# LEDBoard.net
KiCad netlist of a schematic drawn in EAGLE
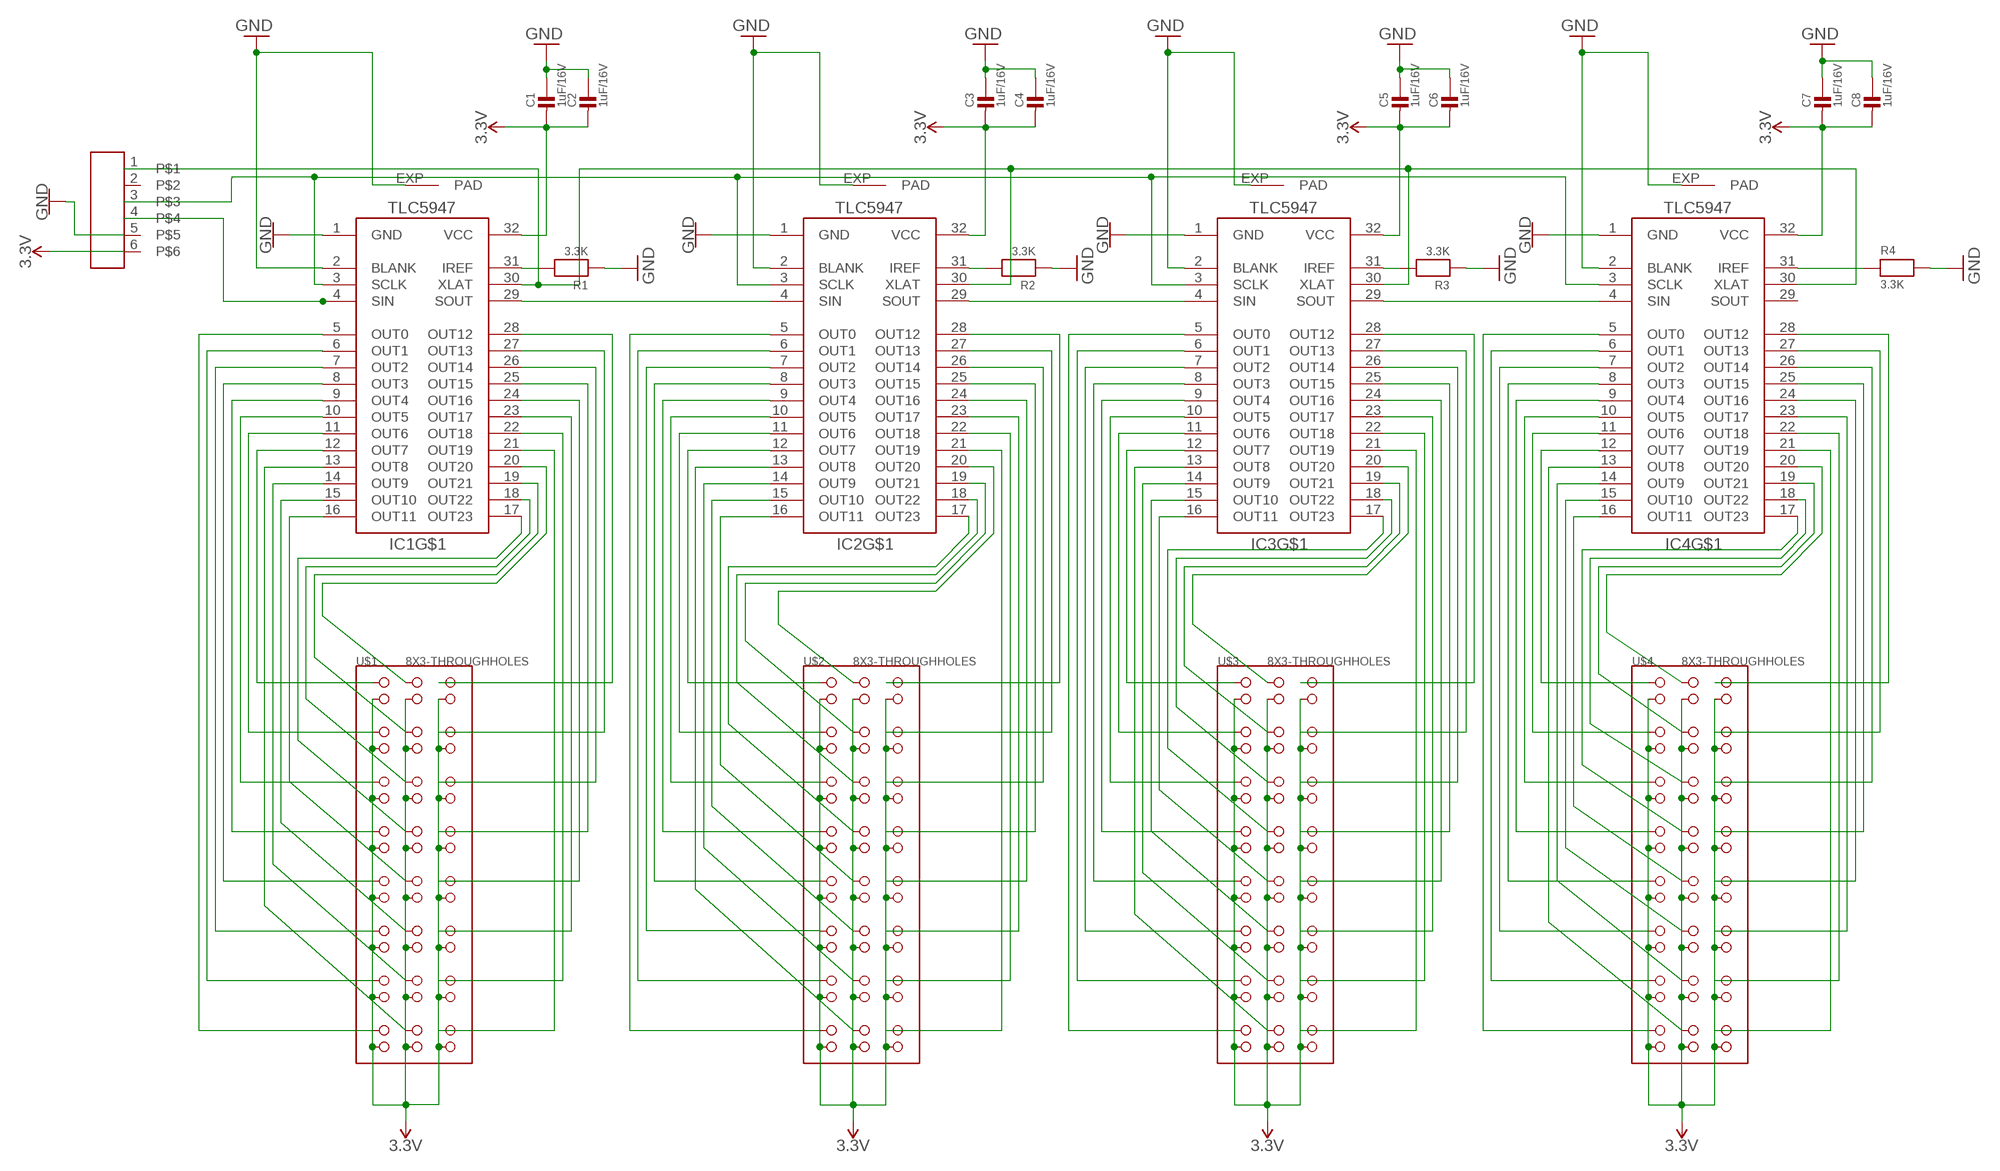
[diagram p0: schematic, sheet 1]

(export (version "E")
  (design (tool "Eeschema 10.0.6"))
  (components
    (comp (ref "C1")
      (value "1uF/16V")
      (footprint "eagle-import:_0805")
      (libsource (lib "eagle-import") (part "CAP_CERAMIC_0805"))
    )
    (comp (ref "C2")
      (value "1uF/16V")
      (footprint "eagle-import:_0805")
      (libsource (lib "eagle-import") (part "CAP_CERAMIC_0805"))
    )
    (comp (ref "C3")
      (value "1uF/16V")
      (footprint "eagle-import:_0805")
      (libsource (lib "eagle-import") (part "CAP_CERAMIC_0805"))
    )
    (comp (ref "C4")
      (value "1uF/16V")
      (footprint "eagle-import:_0805")
      (libsource (lib "eagle-import") (part "CAP_CERAMIC_0805"))
    )
    (comp (ref "C5")
      (value "1uF/16V")
      (footprint "eagle-import:_0805")
      (libsource (lib "eagle-import") (part "CAP_CERAMIC_0805"))
    )
    (comp (ref "C6")
      (value "1uF/16V")
      (footprint "eagle-import:_0805")
      (libsource (lib "eagle-import") (part "CAP_CERAMIC_0805"))
    )
    (comp (ref "C7")
      (value "1uF/16V")
      (footprint "eagle-import:_0805")
      (libsource (lib "eagle-import") (part "CAP_CERAMIC_0805"))
    )
    (comp (ref "C8")
      (value "1uF/16V")
      (footprint "eagle-import:_0805")
      (libsource (lib "eagle-import") (part "CAP_CERAMIC_0805"))
    )
    (comp (ref "IC1")
      (value "TLC5947-DAP")
      (footprint "eagle-import:HTSSOP32DAP")
      (libsource (lib "eagle-import") (part "TLC5947-DAP"))
    )
    (comp (ref "IC2")
      (value "TLC5947-DAP")
      (footprint "eagle-import:HTSSOP32DAP")
      (libsource (lib "eagle-import") (part "TLC5947-DAP"))
    )
    (comp (ref "IC3")
      (value "TLC5947-DAP")
      (footprint "eagle-import:HTSSOP32DAP")
      (libsource (lib "eagle-import") (part "TLC5947-DAP"))
    )
    (comp (ref "IC4")
      (value "TLC5947-DAP")
      (footprint "eagle-import:HTSSOP32DAP")
      (libsource (lib "eagle-import") (part "TLC5947-DAP"))
    )
    (comp (ref "R1")
      (value "3.3K")
      (footprint "eagle-import:_0805")
      (libsource (lib "eagle-import") (part "RESISTOR_0805"))
    )
    (comp (ref "R2")
      (value "3.3K")
      (footprint "eagle-import:_0805")
      (libsource (lib "eagle-import") (part "RESISTOR_0805"))
    )
    (comp (ref "R3")
      (value "3.3K")
      (footprint "eagle-import:_0805")
      (libsource (lib "eagle-import") (part "RESISTOR_0805"))
    )
    (comp (ref "R4")
      (value "3.3K")
      (footprint "eagle-import:_0805")
      (libsource (lib "eagle-import") (part "RESISTOR_0805"))
    )
    (comp (ref "U$1")
      (value "8X3-THROUGHHOLES")
      (footprint "eagle-import:COLUMNOFTHROUGHHOLES")
      (libsource (lib "eagle-import") (part "8X3-THROUGHHOLES"))
    )
    (comp (ref "U$2")
      (value "8X3-THROUGHHOLES")
      (footprint "eagle-import:COLUMNOFTHROUGHHOLES")
      (libsource (lib "eagle-import") (part "8X3-THROUGHHOLES"))
    )
    (comp (ref "U$3")
      (value "8X3-THROUGHHOLES")
      (footprint "eagle-import:COLUMNOFTHROUGHHOLES")
      (libsource (lib "eagle-import") (part "8X3-THROUGHHOLES"))
    )
    (comp (ref "U$4")
      (value "8X3-THROUGHHOLES")
      (footprint "eagle-import:COLUMNOFTHROUGHHOLES")
      (libsource (lib "eagle-import") (part "8X3-THROUGHHOLES"))
    )
    (comp (ref "U$5")
      (value "CONNECTOR_6PIN")
      (footprint "eagle-import:CONNECTOR_6PIN")
      (libsource (lib "eagle-import") (part "CONNECTOR_6PIN"))
    )
  )
  (nets
    (net (code "1") (name "3.3V") (class "Default")
      (node (ref "C1") (pin "2") (pinfunction "P$2_2") (pintype "passive"))
      (node (ref "C2") (pin "2") (pinfunction "P$2_2") (pintype "passive"))
      (node (ref "C3") (pin "2") (pinfunction "P$2_2") (pintype "passive"))
      (node (ref "C4") (pin "2") (pinfunction "P$2_2") (pintype "passive"))
      (node (ref "C5") (pin "2") (pinfunction "P$2_2") (pintype "passive"))
      (node (ref "C6") (pin "2") (pinfunction "P$2_2") (pintype "passive"))
      (node (ref "C7") (pin "2") (pinfunction "P$2_2") (pintype "passive"))
      (node (ref "C8") (pin "2") (pinfunction "P$2_2") (pintype "passive"))
      (node (ref "IC1") (pin "32") (pinfunction "VCC_32") (pintype "power_in"))
      (node (ref "IC2") (pin "32") (pinfunction "VCC_32") (pintype "power_in"))
      (node (ref "IC3") (pin "32") (pinfunction "VCC_32") (pintype "power_in"))
      (node (ref "IC4") (pin "32") (pinfunction "VCC_32") (pintype "power_in"))
      (node (ref "U$1") (pin "V0") (pinfunction "V_V0") (pintype "power_in"))
      (node (ref "U$1") (pin "V1") (pinfunction "V_V1") (pintype "power_in"))
      (node (ref "U$1") (pin "V10") (pinfunction "V_V10") (pintype "power_in"))
      (node (ref "U$1") (pin "V11") (pinfunction "V_V11") (pintype "power_in"))
      (node (ref "U$1") (pin "V12") (pinfunction "V_V12") (pintype "power_in"))
      (node (ref "U$1") (pin "V13") (pinfunction "V_V13") (pintype "power_in"))
      (node (ref "U$1") (pin "V14") (pinfunction "V_V14") (pintype "power_in"))
      (node (ref "U$1") (pin "V15") (pinfunction "V_V15") (pintype "power_in"))
      (node (ref "U$1") (pin "V16") (pinfunction "V_V16") (pintype "power_in"))
      (node (ref "U$1") (pin "V17") (pinfunction "V_V17") (pintype "power_in"))
      (node (ref "U$1") (pin "V18") (pinfunction "V_V18") (pintype "power_in"))
      (node (ref "U$1") (pin "V19") (pinfunction "V_V19") (pintype "power_in"))
      (node (ref "U$1") (pin "V2") (pinfunction "V_V2") (pintype "power_in"))
      (node (ref "U$1") (pin "V20") (pinfunction "V_V20") (pintype "power_in"))
      (node (ref "U$1") (pin "V21") (pinfunction "V_V21") (pintype "power_in"))
      (node (ref "U$1") (pin "V22") (pinfunction "V_V22") (pintype "power_in"))
      (node (ref "U$1") (pin "V23") (pinfunction "V_V23") (pintype "power_in"))
      (node (ref "U$1") (pin "V3") (pinfunction "V_V3") (pintype "power_in"))
      (node (ref "U$1") (pin "V4") (pinfunction "V_V4") (pintype "power_in"))
      (node (ref "U$1") (pin "V5") (pinfunction "V_V5") (pintype "power_in"))
      (node (ref "U$1") (pin "V6") (pinfunction "V_V6") (pintype "power_in"))
      (node (ref "U$1") (pin "V7") (pinfunction "V_V7") (pintype "power_in"))
      (node (ref "U$1") (pin "V8") (pinfunction "V_V8") (pintype "power_in"))
      (node (ref "U$1") (pin "V9") (pinfunction "V_V9") (pintype "power_in"))
      (node (ref "U$2") (pin "V0") (pinfunction "V_V0") (pintype "power_in"))
      (node (ref "U$2") (pin "V1") (pinfunction "V_V1") (pintype "power_in"))
      (node (ref "U$2") (pin "V10") (pinfunction "V_V10") (pintype "power_in"))
      (node (ref "U$2") (pin "V11") (pinfunction "V_V11") (pintype "power_in"))
      (node (ref "U$2") (pin "V12") (pinfunction "V_V12") (pintype "power_in"))
      (node (ref "U$2") (pin "V13") (pinfunction "V_V13") (pintype "power_in"))
      (node (ref "U$2") (pin "V14") (pinfunction "V_V14") (pintype "power_in"))
      (node (ref "U$2") (pin "V15") (pinfunction "V_V15") (pintype "power_in"))
      (node (ref "U$2") (pin "V16") (pinfunction "V_V16") (pintype "power_in"))
      (node (ref "U$2") (pin "V17") (pinfunction "V_V17") (pintype "power_in"))
      (node (ref "U$2") (pin "V18") (pinfunction "V_V18") (pintype "power_in"))
      (node (ref "U$2") (pin "V19") (pinfunction "V_V19") (pintype "power_in"))
      (node (ref "U$2") (pin "V2") (pinfunction "V_V2") (pintype "power_in"))
      (node (ref "U$2") (pin "V20") (pinfunction "V_V20") (pintype "power_in"))
      (node (ref "U$2") (pin "V21") (pinfunction "V_V21") (pintype "power_in"))
      (node (ref "U$2") (pin "V22") (pinfunction "V_V22") (pintype "power_in"))
      (node (ref "U$2") (pin "V23") (pinfunction "V_V23") (pintype "power_in"))
      (node (ref "U$2") (pin "V3") (pinfunction "V_V3") (pintype "power_in"))
      (node (ref "U$2") (pin "V4") (pinfunction "V_V4") (pintype "power_in"))
      (node (ref "U$2") (pin "V5") (pinfunction "V_V5") (pintype "power_in"))
      (node (ref "U$2") (pin "V6") (pinfunction "V_V6") (pintype "power_in"))
      (node (ref "U$2") (pin "V7") (pinfunction "V_V7") (pintype "power_in"))
      (node (ref "U$2") (pin "V8") (pinfunction "V_V8") (pintype "power_in"))
      (node (ref "U$2") (pin "V9") (pinfunction "V_V9") (pintype "power_in"))
      (node (ref "U$3") (pin "V0") (pinfunction "V_V0") (pintype "power_in"))
      (node (ref "U$3") (pin "V1") (pinfunction "V_V1") (pintype "power_in"))
      (node (ref "U$3") (pin "V10") (pinfunction "V_V10") (pintype "power_in"))
      (node (ref "U$3") (pin "V11") (pinfunction "V_V11") (pintype "power_in"))
      (node (ref "U$3") (pin "V12") (pinfunction "V_V12") (pintype "power_in"))
      (node (ref "U$3") (pin "V13") (pinfunction "V_V13") (pintype "power_in"))
      (node (ref "U$3") (pin "V14") (pinfunction "V_V14") (pintype "power_in"))
      (node (ref "U$3") (pin "V15") (pinfunction "V_V15") (pintype "power_in"))
      (node (ref "U$3") (pin "V16") (pinfunction "V_V16") (pintype "power_in"))
      (node (ref "U$3") (pin "V17") (pinfunction "V_V17") (pintype "power_in"))
      (node (ref "U$3") (pin "V18") (pinfunction "V_V18") (pintype "power_in"))
      (node (ref "U$3") (pin "V19") (pinfunction "V_V19") (pintype "power_in"))
      (node (ref "U$3") (pin "V2") (pinfunction "V_V2") (pintype "power_in"))
      (node (ref "U$3") (pin "V20") (pinfunction "V_V20") (pintype "power_in"))
      (node (ref "U$3") (pin "V21") (pinfunction "V_V21") (pintype "power_in"))
      (node (ref "U$3") (pin "V22") (pinfunction "V_V22") (pintype "power_in"))
      (node (ref "U$3") (pin "V23") (pinfunction "V_V23") (pintype "power_in"))
      (node (ref "U$3") (pin "V3") (pinfunction "V_V3") (pintype "power_in"))
      (node (ref "U$3") (pin "V4") (pinfunction "V_V4") (pintype "power_in"))
      (node (ref "U$3") (pin "V5") (pinfunction "V_V5") (pintype "power_in"))
      (node (ref "U$3") (pin "V6") (pinfunction "V_V6") (pintype "power_in"))
      (node (ref "U$3") (pin "V7") (pinfunction "V_V7") (pintype "power_in"))
      (node (ref "U$3") (pin "V8") (pinfunction "V_V8") (pintype "power_in"))
      (node (ref "U$3") (pin "V9") (pinfunction "V_V9") (pintype "power_in"))
      (node (ref "U$4") (pin "V0") (pinfunction "V_V0") (pintype "power_in"))
      (node (ref "U$4") (pin "V1") (pinfunction "V_V1") (pintype "power_in"))
      (node (ref "U$4") (pin "V10") (pinfunction "V_V10") (pintype "power_in"))
      (node (ref "U$4") (pin "V11") (pinfunction "V_V11") (pintype "power_in"))
      (node (ref "U$4") (pin "V12") (pinfunction "V_V12") (pintype "power_in"))
      (node (ref "U$4") (pin "V13") (pinfunction "V_V13") (pintype "power_in"))
      (node (ref "U$4") (pin "V14") (pinfunction "V_V14") (pintype "power_in"))
      (node (ref "U$4") (pin "V15") (pinfunction "V_V15") (pintype "power_in"))
      (node (ref "U$4") (pin "V16") (pinfunction "V_V16") (pintype "power_in"))
      (node (ref "U$4") (pin "V17") (pinfunction "V_V17") (pintype "power_in"))
      (node (ref "U$4") (pin "V18") (pinfunction "V_V18") (pintype "power_in"))
      (node (ref "U$4") (pin "V19") (pinfunction "V_V19") (pintype "power_in"))
      (node (ref "U$4") (pin "V2") (pinfunction "V_V2") (pintype "power_in"))
      (node (ref "U$4") (pin "V20") (pinfunction "V_V20") (pintype "power_in"))
      (node (ref "U$4") (pin "V21") (pinfunction "V_V21") (pintype "power_in"))
      (node (ref "U$4") (pin "V22") (pinfunction "V_V22") (pintype "power_in"))
      (node (ref "U$4") (pin "V23") (pinfunction "V_V23") (pintype "power_in"))
      (node (ref "U$4") (pin "V3") (pinfunction "V_V3") (pintype "power_in"))
      (node (ref "U$4") (pin "V4") (pinfunction "V_V4") (pintype "power_in"))
      (node (ref "U$4") (pin "V5") (pinfunction "V_V5") (pintype "power_in"))
      (node (ref "U$4") (pin "V6") (pinfunction "V_V6") (pintype "power_in"))
      (node (ref "U$4") (pin "V7") (pinfunction "V_V7") (pintype "power_in"))
      (node (ref "U$4") (pin "V8") (pinfunction "V_V8") (pintype "power_in"))
      (node (ref "U$4") (pin "V9") (pinfunction "V_V9") (pintype "power_in"))
      (node (ref "U$5") (pin "6") (pinfunction "P$6_6") (pintype "bidirectional"))
    )
    (net (code "2") (name "GND") (class "Default")
      (node (ref "C1") (pin "1") (pinfunction "P$1_1") (pintype "passive"))
      (node (ref "C2") (pin "1") (pinfunction "P$1_1") (pintype "passive"))
      (node (ref "C3") (pin "1") (pinfunction "P$1_1") (pintype "passive"))
      (node (ref "C4") (pin "1") (pinfunction "P$1_1") (pintype "passive"))
      (node (ref "C5") (pin "1") (pinfunction "P$1_1") (pintype "passive"))
      (node (ref "C6") (pin "1") (pinfunction "P$1_1") (pintype "passive"))
      (node (ref "C7") (pin "1") (pinfunction "P$1_1") (pintype "passive"))
      (node (ref "C8") (pin "1") (pinfunction "P$1_1") (pintype "passive"))
      (node (ref "IC1") (pin "1") (pinfunction "GND_1") (pintype "power_in"))
      (node (ref "IC1") (pin "2") (pinfunction "BLANK_2") (pintype "input"))
      (node (ref "IC1") (pin "EXP") (pinfunction "PAD_EXP") (pintype "passive"))
      (node (ref "IC2") (pin "1") (pinfunction "GND_1") (pintype "power_in"))
      (node (ref "IC2") (pin "2") (pinfunction "BLANK_2") (pintype "input"))
      (node (ref "IC2") (pin "EXP") (pinfunction "PAD_EXP") (pintype "passive"))
      (node (ref "IC3") (pin "1") (pinfunction "GND_1") (pintype "power_in"))
      (node (ref "IC3") (pin "2") (pinfunction "BLANK_2") (pintype "input"))
      (node (ref "IC3") (pin "EXP") (pinfunction "PAD_EXP") (pintype "passive"))
      (node (ref "IC4") (pin "1") (pinfunction "GND_1") (pintype "power_in"))
      (node (ref "IC4") (pin "2") (pinfunction "BLANK_2") (pintype "input"))
      (node (ref "IC4") (pin "EXP") (pinfunction "PAD_EXP") (pintype "passive"))
      (node (ref "R1") (pin "1") (pinfunction "1_1") (pintype "passive"))
      (node (ref "R2") (pin "1") (pinfunction "1_1") (pintype "passive"))
      (node (ref "R3") (pin "1") (pinfunction "1_1") (pintype "passive"))
      (node (ref "R4") (pin "2") (pinfunction "2_2") (pintype "passive"))
      (node (ref "U$5") (pin "5") (pinfunction "P$5_5") (pintype "bidirectional"))
    )
    (net (code "3") (name "Net-(IC1A-IREF)") (class "Default")
      (node (ref "IC1") (pin "31") (pinfunction "IREF_31") (pintype "bidirectional"))
      (node (ref "R1") (pin "2") (pinfunction "2_2") (pintype "passive"))
    )
    (net (code "4") (name "Net-(IC1A-OUT0)") (class "Default")
      (node (ref "IC1") (pin "5") (pinfunction "OUT0_5") (pintype "open_collector"))
      (node (ref "U$1") (pin "0") (pinfunction "0_0") (pintype "power_in"))
    )
    (net (code "5") (name "Net-(IC1A-OUT1)") (class "Default")
      (node (ref "IC1") (pin "6") (pinfunction "OUT1_6") (pintype "open_collector"))
      (node (ref "U$1") (pin "1") (pinfunction "1_1") (pintype "power_in"))
    )
    (net (code "6") (name "Net-(IC1A-OUT2)") (class "Default")
      (node (ref "IC1") (pin "7") (pinfunction "OUT2_7") (pintype "open_collector"))
      (node (ref "U$1") (pin "2") (pinfunction "2_2") (pintype "power_in"))
    )
    (net (code "7") (name "Net-(IC1A-OUT3)") (class "Default")
      (node (ref "IC1") (pin "8") (pinfunction "OUT3_8") (pintype "open_collector"))
      (node (ref "U$1") (pin "3") (pinfunction "3_3") (pintype "power_in"))
    )
    (net (code "8") (name "Net-(IC1A-OUT4)") (class "Default")
      (node (ref "IC1") (pin "9") (pinfunction "OUT4_9") (pintype "open_collector"))
      (node (ref "U$1") (pin "4") (pinfunction "4_4") (pintype "power_in"))
    )
    (net (code "9") (name "Net-(IC1A-OUT5)") (class "Default")
      (node (ref "IC1") (pin "10") (pinfunction "OUT5_10") (pintype "open_collector"))
      (node (ref "U$1") (pin "5") (pinfunction "5_5") (pintype "power_in"))
    )
    (net (code "10") (name "Net-(IC1A-OUT6)") (class "Default")
      (node (ref "IC1") (pin "11") (pinfunction "OUT6_11") (pintype "open_collector"))
      (node (ref "U$1") (pin "6") (pinfunction "6_6") (pintype "power_in"))
    )
    (net (code "11") (name "Net-(IC1A-OUT7)") (class "Default")
      (node (ref "IC1") (pin "12") (pinfunction "OUT7_12") (pintype "open_collector"))
      (node (ref "U$1") (pin "7") (pinfunction "7_7") (pintype "power_in"))
    )
    (net (code "12") (name "Net-(IC1A-OUT8)") (class "Default")
      (node (ref "IC1") (pin "13") (pinfunction "OUT8_13") (pintype "open_collector"))
      (node (ref "U$1") (pin "8") (pinfunction "8_8") (pintype "power_in"))
    )
    (net (code "13") (name "Net-(IC1A-OUT9)") (class "Default")
      (node (ref "IC1") (pin "14") (pinfunction "OUT9_14") (pintype "open_collector"))
      (node (ref "U$1") (pin "9") (pinfunction "9_9") (pintype "power_in"))
    )
    (net (code "14") (name "Net-(IC1A-OUT10)") (class "Default")
      (node (ref "IC1") (pin "15") (pinfunction "OUT10_15") (pintype "open_collector"))
      (node (ref "U$1") (pin "10") (pinfunction "10_10") (pintype "power_in"))
    )
    (net (code "15") (name "Net-(IC1A-OUT11)") (class "Default")
      (node (ref "IC1") (pin "16") (pinfunction "OUT11_16") (pintype "open_collector"))
      (node (ref "U$1") (pin "11") (pinfunction "11_11") (pintype "power_in"))
    )
    (net (code "16") (name "Net-(IC1A-OUT12)") (class "Default")
      (node (ref "IC1") (pin "28") (pinfunction "OUT12_28") (pintype "open_collector"))
      (node (ref "U$1") (pin "23") (pinfunction "23_23") (pintype "power_in"))
    )
    (net (code "17") (name "Net-(IC1A-OUT13)") (class "Default")
      (node (ref "IC1") (pin "27") (pinfunction "OUT13_27") (pintype "open_collector"))
      (node (ref "U$1") (pin "22") (pinfunction "22_22") (pintype "power_in"))
    )
    (net (code "18") (name "Net-(IC1A-OUT14)") (class "Default")
      (node (ref "IC1") (pin "26") (pinfunction "OUT14_26") (pintype "open_collector"))
      (node (ref "U$1") (pin "21") (pinfunction "21_21") (pintype "power_in"))
    )
    (net (code "19") (name "Net-(IC1A-OUT15)") (class "Default")
      (node (ref "IC1") (pin "25") (pinfunction "OUT15_25") (pintype "open_collector"))
      (node (ref "U$1") (pin "20") (pinfunction "20_20") (pintype "power_in"))
    )
    (net (code "20") (name "Net-(IC1A-OUT16)") (class "Default")
      (node (ref "IC1") (pin "24") (pinfunction "OUT16_24") (pintype "open_collector"))
      (node (ref "U$1") (pin "19") (pinfunction "19_19") (pintype "power_in"))
    )
    (net (code "21") (name "Net-(IC1A-OUT17)") (class "Default")
      (node (ref "IC1") (pin "23") (pinfunction "OUT17_23") (pintype "open_collector"))
      (node (ref "U$1") (pin "18") (pinfunction "18_18") (pintype "power_in"))
    )
    (net (code "22") (name "Net-(IC1A-OUT18)") (class "Default")
      (node (ref "IC1") (pin "22") (pinfunction "OUT18_22") (pintype "open_collector"))
      (node (ref "U$1") (pin "17") (pinfunction "17_17") (pintype "power_in"))
    )
    (net (code "23") (name "Net-(IC1A-OUT19)") (class "Default")
      (node (ref "IC1") (pin "21") (pinfunction "OUT19_21") (pintype "open_collector"))
      (node (ref "U$1") (pin "16") (pinfunction "16_16") (pintype "power_in"))
    )
    (net (code "24") (name "Net-(IC1A-OUT20)") (class "Default")
      (node (ref "IC1") (pin "20") (pinfunction "OUT20_20") (pintype "open_collector"))
      (node (ref "U$1") (pin "15") (pinfunction "15_15") (pintype "power_in"))
    )
    (net (code "25") (name "Net-(IC1A-OUT21)") (class "Default")
      (node (ref "IC1") (pin "19") (pinfunction "OUT21_19") (pintype "open_collector"))
      (node (ref "U$1") (pin "14") (pinfunction "14_14") (pintype "power_in"))
    )
    (net (code "26") (name "Net-(IC1A-OUT22)") (class "Default")
      (node (ref "IC1") (pin "18") (pinfunction "OUT22_18") (pintype "open_collector"))
      (node (ref "U$1") (pin "13") (pinfunction "13_13") (pintype "power_in"))
    )
    (net (code "27") (name "Net-(IC1A-OUT23)") (class "Default")
      (node (ref "IC1") (pin "17") (pinfunction "OUT23_17") (pintype "open_collector"))
      (node (ref "U$1") (pin "12") (pinfunction "12_12") (pintype "power_in"))
    )
    (net (code "28") (name "Net-(IC1A-SCLK)") (class "Default")
      (node (ref "IC1") (pin "3") (pinfunction "SCLK_3") (pintype "input"))
      (node (ref "IC2") (pin "3") (pinfunction "SCLK_3") (pintype "input"))
      (node (ref "IC3") (pin "3") (pinfunction "SCLK_3") (pintype "input"))
      (node (ref "IC4") (pin "3") (pinfunction "SCLK_3") (pintype "input"))
      (node (ref "U$5") (pin "3") (pinfunction "P$3_3") (pintype "bidirectional"))
    )
    (net (code "29") (name "Net-(IC1A-SIN)") (class "Default")
      (node (ref "IC1") (pin "4") (pinfunction "SIN_4") (pintype "input"))
      (node (ref "U$5") (pin "4") (pinfunction "P$4_4") (pintype "bidirectional"))
    )
    (net (code "30") (name "Net-(IC1A-SOUT)") (class "Default")
      (node (ref "IC1") (pin "29") (pinfunction "SOUT_29") (pintype "output"))
      (node (ref "IC2") (pin "4") (pinfunction "SIN_4") (pintype "input"))
    )
    (net (code "31") (name "Net-(IC1A-XLAT)") (class "Default")
      (node (ref "IC1") (pin "30") (pinfunction "XLAT_30") (pintype "input"))
      (node (ref "IC2") (pin "30") (pinfunction "XLAT_30") (pintype "input"))
      (node (ref "IC3") (pin "30") (pinfunction "XLAT_30") (pintype "input"))
      (node (ref "IC4") (pin "30") (pinfunction "XLAT_30") (pintype "input"))
      (node (ref "U$5") (pin "1") (pinfunction "P$1_1") (pintype "bidirectional"))
    )
    (net (code "32") (name "Net-(IC2A-IREF)") (class "Default")
      (node (ref "IC2") (pin "31") (pinfunction "IREF_31") (pintype "bidirectional"))
      (node (ref "R2") (pin "2") (pinfunction "2_2") (pintype "passive"))
    )
    (net (code "33") (name "Net-(IC2A-OUT0)") (class "Default")
      (node (ref "IC2") (pin "5") (pinfunction "OUT0_5") (pintype "open_collector"))
      (node (ref "U$2") (pin "0") (pinfunction "0_0") (pintype "power_in"))
    )
    (net (code "34") (name "Net-(IC2A-OUT1)") (class "Default")
      (node (ref "IC2") (pin "6") (pinfunction "OUT1_6") (pintype "open_collector"))
      (node (ref "U$2") (pin "1") (pinfunction "1_1") (pintype "power_in"))
    )
    (net (code "35") (name "Net-(IC2A-OUT2)") (class "Default")
      (node (ref "IC2") (pin "7") (pinfunction "OUT2_7") (pintype "open_collector"))
      (node (ref "U$2") (pin "2") (pinfunction "2_2") (pintype "power_in"))
    )
    (net (code "36") (name "Net-(IC2A-OUT3)") (class "Default")
      (node (ref "IC2") (pin "8") (pinfunction "OUT3_8") (pintype "open_collector"))
      (node (ref "U$2") (pin "3") (pinfunction "3_3") (pintype "power_in"))
    )
    (net (code "37") (name "Net-(IC2A-OUT4)") (class "Default")
      (node (ref "IC2") (pin "9") (pinfunction "OUT4_9") (pintype "open_collector"))
      (node (ref "U$2") (pin "4") (pinfunction "4_4") (pintype "power_in"))
    )
    (net (code "38") (name "Net-(IC2A-OUT5)") (class "Default")
      (node (ref "IC2") (pin "10") (pinfunction "OUT5_10") (pintype "open_collector"))
      (node (ref "U$2") (pin "5") (pinfunction "5_5") (pintype "power_in"))
    )
    (net (code "39") (name "Net-(IC2A-OUT6)") (class "Default")
      (node (ref "IC2") (pin "11") (pinfunction "OUT6_11") (pintype "open_collector"))
      (node (ref "U$2") (pin "6") (pinfunction "6_6") (pintype "power_in"))
    )
    (net (code "40") (name "Net-(IC2A-OUT7)") (class "Default")
      (node (ref "IC2") (pin "12") (pinfunction "OUT7_12") (pintype "open_collector"))
      (node (ref "U$2") (pin "7") (pinfunction "7_7") (pintype "power_in"))
    )
    (net (code "41") (name "Net-(IC2A-OUT8)") (class "Default")
      (node (ref "IC2") (pin "13") (pinfunction "OUT8_13") (pintype "open_collector"))
      (node (ref "U$2") (pin "8") (pinfunction "8_8") (pintype "power_in"))
    )
    (net (code "42") (name "Net-(IC2A-OUT9)") (class "Default")
      (node (ref "IC2") (pin "14") (pinfunction "OUT9_14") (pintype "open_collector"))
      (node (ref "U$2") (pin "9") (pinfunction "9_9") (pintype "power_in"))
    )
    (net (code "43") (name "Net-(IC2A-OUT10)") (class "Default")
      (node (ref "IC2") (pin "15") (pinfunction "OUT10_15") (pintype "open_collector"))
      (node (ref "U$2") (pin "10") (pinfunction "10_10") (pintype "power_in"))
    )
    (net (code "44") (name "Net-(IC2A-OUT11)") (class "Default")
      (node (ref "IC2") (pin "16") (pinfunction "OUT11_16") (pintype "open_collector"))
      (node (ref "U$2") (pin "11") (pinfunction "11_11") (pintype "power_in"))
    )
    (net (code "45") (name "Net-(IC2A-OUT12)") (class "Default")
      (node (ref "IC2") (pin "28") (pinfunction "OUT12_28") (pintype "open_collector"))
      (node (ref "U$2") (pin "23") (pinfunction "23_23") (pintype "power_in"))
    )
    (net (code "46") (name "Net-(IC2A-OUT13)") (class "Default")
      (node (ref "IC2") (pin "27") (pinfunction "OUT13_27") (pintype "open_collector"))
      (node (ref "U$2") (pin "22") (pinfunction "22_22") (pintype "power_in"))
    )
    (net (code "47") (name "Net-(IC2A-OUT14)") (class "Default")
      (node (ref "IC2") (pin "26") (pinfunction "OUT14_26") (pintype "open_collector"))
      (node (ref "U$2") (pin "21") (pinfunction "21_21") (pintype "power_in"))
    )
    (net (code "48") (name "Net-(IC2A-OUT15)") (class "Default")
      (node (ref "IC2") (pin "25") (pinfunction "OUT15_25") (pintype "open_collector"))
      (node (ref "U$2") (pin "20") (pinfunction "20_20") (pintype "power_in"))
    )
    (net (code "49") (name "Net-(IC2A-OUT16)") (class "Default")
      (node (ref "IC2") (pin "24") (pinfunction "OUT16_24") (pintype "open_collector"))
      (node (ref "U$2") (pin "19") (pinfunction "19_19") (pintype "power_in"))
    )
    (net (code "50") (name "Net-(IC2A-OUT17)") (class "Default")
      (node (ref "IC2") (pin "23") (pinfunction "OUT17_23") (pintype "open_collector"))
      (node (ref "U$2") (pin "18") (pinfunction "18_18") (pintype "power_in"))
    )
    (net (code "51") (name "Net-(IC2A-OUT18)") (class "Default")
      (node (ref "IC2") (pin "22") (pinfunction "OUT18_22") (pintype "open_collector"))
      (node (ref "U$2") (pin "17") (pinfunction "17_17") (pintype "power_in"))
    )
    (net (code "52") (name "Net-(IC2A-OUT19)") (class "Default")
      (node (ref "IC2") (pin "21") (pinfunction "OUT19_21") (pintype "open_collector"))
      (node (ref "U$2") (pin "16") (pinfunction "16_16") (pintype "power_in"))
    )
    (net (code "53") (name "Net-(IC2A-OUT20)") (class "Default")
      (node (ref "IC2") (pin "20") (pinfunction "OUT20_20") (pintype "open_collector"))
      (node (ref "U$2") (pin "15") (pinfunction "15_15") (pintype "power_in"))
    )
    (net (code "54") (name "Net-(IC2A-OUT21)") (class "Default")
      (node (ref "IC2") (pin "19") (pinfunction "OUT21_19") (pintype "open_collector"))
      (node (ref "U$2") (pin "14") (pinfunction "14_14") (pintype "power_in"))
    )
    (net (code "55") (name "Net-(IC2A-OUT22)") (class "Default")
      (node (ref "IC2") (pin "18") (pinfunction "OUT22_18") (pintype "open_collector"))
      (node (ref "U$2") (pin "13") (pinfunction "13_13") (pintype "power_in"))
    )
    (net (code "56") (name "Net-(IC2A-OUT23)") (class "Default")
      (node (ref "IC2") (pin "17") (pinfunction "OUT23_17") (pintype "open_collector"))
      (node (ref "U$2") (pin "12") (pinfunction "12_12") (pintype "power_in"))
    )
    (net (code "57") (name "Net-(IC2A-SOUT)") (class "Default")
      (node (ref "IC2") (pin "29") (pinfunction "SOUT_29") (pintype "output"))
      (node (ref "IC3") (pin "4") (pinfunction "SIN_4") (pintype "input"))
    )
    (net (code "58") (name "Net-(IC3A-IREF)") (class "Default")
      (node (ref "IC3") (pin "31") (pinfunction "IREF_31") (pintype "bidirectional"))
      (node (ref "R3") (pin "2") (pinfunction "2_2") (pintype "passive"))
    )
    (net (code "59") (name "Net-(IC3A-OUT0)") (class "Default")
      (node (ref "IC3") (pin "5") (pinfunction "OUT0_5") (pintype "open_collector"))
      (node (ref "U$3") (pin "0") (pinfunction "0_0") (pintype "power_in"))
    )
    (net (code "60") (name "Net-(IC3A-OUT1)") (class "Default")
      (node (ref "IC3") (pin "6") (pinfunction "OUT1_6") (pintype "open_collector"))
      (node (ref "U$3") (pin "1") (pinfunction "1_1") (pintype "power_in"))
    )
    (net (code "61") (name "Net-(IC3A-OUT2)") (class "Default")
      (node (ref "IC3") (pin "7") (pinfunction "OUT2_7") (pintype "open_collector"))
      (node (ref "U$3") (pin "2") (pinfunction "2_2") (pintype "power_in"))
    )
    (net (code "62") (name "Net-(IC3A-OUT3)") (class "Default")
      (node (ref "IC3") (pin "8") (pinfunction "OUT3_8") (pintype "open_collector"))
      (node (ref "U$3") (pin "3") (pinfunction "3_3") (pintype "power_in"))
    )
    (net (code "63") (name "Net-(IC3A-OUT4)") (class "Default")
      (node (ref "IC3") (pin "9") (pinfunction "OUT4_9") (pintype "open_collector"))
      (node (ref "U$3") (pin "4") (pinfunction "4_4") (pintype "power_in"))
    )
    (net (code "64") (name "Net-(IC3A-OUT5)") (class "Default")
      (node (ref "IC3") (pin "10") (pinfunction "OUT5_10") (pintype "open_collector"))
      (node (ref "U$3") (pin "5") (pinfunction "5_5") (pintype "power_in"))
    )
    (net (code "65") (name "Net-(IC3A-OUT6)") (class "Default")
      (node (ref "IC3") (pin "11") (pinfunction "OUT6_11") (pintype "open_collector"))
      (node (ref "U$3") (pin "6") (pinfunction "6_6") (pintype "power_in"))
    )
    (net (code "66") (name "Net-(IC3A-OUT7)") (class "Default")
      (node (ref "IC3") (pin "12") (pinfunction "OUT7_12") (pintype "open_collector"))
      (node (ref "U$3") (pin "7") (pinfunction "7_7") (pintype "power_in"))
    )
    (net (code "67") (name "Net-(IC3A-OUT8)") (class "Default")
      (node (ref "IC3") (pin "13") (pinfunction "OUT8_13") (pintype "open_collector"))
      (node (ref "U$3") (pin "8") (pinfunction "8_8") (pintype "power_in"))
    )
    (net (code "68") (name "Net-(IC3A-OUT9)") (class "Default")
      (node (ref "IC3") (pin "14") (pinfunction "OUT9_14") (pintype "open_collector"))
      (node (ref "U$3") (pin "9") (pinfunction "9_9") (pintype "power_in"))
    )
    (net (code "69") (name "Net-(IC3A-OUT10)") (class "Default")
      (node (ref "IC3") (pin "15") (pinfunction "OUT10_15") (pintype "open_collector"))
      (node (ref "U$3") (pin "10") (pinfunction "10_10") (pintype "power_in"))
    )
    (net (code "70") (name "Net-(IC3A-OUT11)") (class "Default")
      (node (ref "IC3") (pin "16") (pinfunction "OUT11_16") (pintype "open_collector"))
      (node (ref "U$3") (pin "11") (pinfunction "11_11") (pintype "power_in"))
    )
    (net (code "71") (name "Net-(IC3A-OUT12)") (class "Default")
      (node (ref "IC3") (pin "28") (pinfunction "OUT12_28") (pintype "open_collector"))
      (node (ref "U$3") (pin "23") (pinfunction "23_23") (pintype "power_in"))
    )
    (net (code "72") (name "Net-(IC3A-OUT13)") (class "Default")
      (node (ref "IC3") (pin "27") (pinfunction "OUT13_27") (pintype "open_collector"))
      (node (ref "U$3") (pin "22") (pinfunction "22_22") (pintype "power_in"))
    )
    (net (code "73") (name "Net-(IC3A-OUT14)") (class "Default")
      (node (ref "IC3") (pin "26") (pinfunction "OUT14_26") (pintype "open_collector"))
      (node (ref "U$3") (pin "21") (pinfunction "21_21") (pintype "power_in"))
    )
    (net (code "74") (name "Net-(IC3A-OUT15)") (class "Default")
      (node (ref "IC3") (pin "25") (pinfunction "OUT15_25") (pintype "open_collector"))
      (node (ref "U$3") (pin "20") (pinfunction "20_20") (pintype "power_in"))
    )
    (net (code "75") (name "Net-(IC3A-OUT16)") (class "Default")
      (node (ref "IC3") (pin "24") (pinfunction "OUT16_24") (pintype "open_collector"))
      (node (ref "U$3") (pin "19") (pinfunction "19_19") (pintype "power_in"))
    )
    (net (code "76") (name "Net-(IC3A-OUT17)") (class "Default")
      (node (ref "IC3") (pin "23") (pinfunction "OUT17_23") (pintype "open_collector"))
      (node (ref "U$3") (pin "18") (pinfunction "18_18") (pintype "power_in"))
    )
    (net (code "77") (name "Net-(IC3A-OUT18)") (class "Default")
      (node (ref "IC3") (pin "22") (pinfunction "OUT18_22") (pintype "open_collector"))
      (node (ref "U$3") (pin "17") (pinfunction "17_17") (pintype "power_in"))
    )
    (net (code "78") (name "Net-(IC3A-OUT19)") (class "Default")
      (node (ref "IC3") (pin "21") (pinfunction "OUT19_21") (pintype "open_collector"))
      (node (ref "U$3") (pin "16") (pinfunction "16_16") (pintype "power_in"))
    )
    (net (code "79") (name "Net-(IC3A-OUT20)") (class "Default")
      (node (ref "IC3") (pin "20") (pinfunction "OUT20_20") (pintype "open_collector"))
      (node (ref "U$3") (pin "15") (pinfunction "15_15") (pintype "power_in"))
    )
    (net (code "80") (name "Net-(IC3A-OUT21)") (class "Default")
      (node (ref "IC3") (pin "19") (pinfunction "OUT21_19") (pintype "open_collector"))
      (node (ref "U$3") (pin "14") (pinfunction "14_14") (pintype "power_in"))
    )
    (net (code "81") (name "Net-(IC3A-OUT22)") (class "Default")
      (node (ref "IC3") (pin "18") (pinfunction "OUT22_18") (pintype "open_collector"))
      (node (ref "U$3") (pin "13") (pinfunction "13_13") (pintype "power_in"))
    )
    (net (code "82") (name "Net-(IC3A-OUT23)") (class "Default")
      (node (ref "IC3") (pin "17") (pinfunction "OUT23_17") (pintype "open_collector"))
      (node (ref "U$3") (pin "12") (pinfunction "12_12") (pintype "power_in"))
    )
    (net (code "83") (name "Net-(IC3A-SOUT)") (class "Default")
      (node (ref "IC3") (pin "29") (pinfunction "SOUT_29") (pintype "output"))
      (node (ref "IC4") (pin "4") (pinfunction "SIN_4") (pintype "input"))
    )
    (net (code "84") (name "Net-(IC4A-IREF)") (class "Default")
      (node (ref "IC4") (pin "31") (pinfunction "IREF_31") (pintype "bidirectional"))
      (node (ref "R4") (pin "1") (pinfunction "1_1") (pintype "passive"))
    )
    (net (code "85") (name "Net-(IC4A-OUT0)") (class "Default")
      (node (ref "IC4") (pin "5") (pinfunction "OUT0_5") (pintype "open_collector"))
      (node (ref "U$4") (pin "0") (pinfunction "0_0") (pintype "power_in"))
    )
    (net (code "86") (name "Net-(IC4A-OUT1)") (class "Default")
      (node (ref "IC4") (pin "6") (pinfunction "OUT1_6") (pintype "open_collector"))
      (node (ref "U$4") (pin "1") (pinfunction "1_1") (pintype "power_in"))
    )
    (net (code "87") (name "Net-(IC4A-OUT2)") (class "Default")
      (node (ref "IC4") (pin "7") (pinfunction "OUT2_7") (pintype "open_collector"))
      (node (ref "U$4") (pin "2") (pinfunction "2_2") (pintype "power_in"))
    )
    (net (code "88") (name "Net-(IC4A-OUT3)") (class "Default")
      (node (ref "IC4") (pin "8") (pinfunction "OUT3_8") (pintype "open_collector"))
      (node (ref "U$4") (pin "3") (pinfunction "3_3") (pintype "power_in"))
    )
    (net (code "89") (name "Net-(IC4A-OUT4)") (class "Default")
      (node (ref "IC4") (pin "9") (pinfunction "OUT4_9") (pintype "open_collector"))
      (node (ref "U$4") (pin "4") (pinfunction "4_4") (pintype "power_in"))
    )
    (net (code "90") (name "Net-(IC4A-OUT5)") (class "Default")
      (node (ref "IC4") (pin "10") (pinfunction "OUT5_10") (pintype "open_collector"))
      (node (ref "U$4") (pin "5") (pinfunction "5_5") (pintype "power_in"))
    )
    (net (code "91") (name "Net-(IC4A-OUT6)") (class "Default")
      (node (ref "IC4") (pin "11") (pinfunction "OUT6_11") (pintype "open_collector"))
      (node (ref "U$4") (pin "6") (pinfunction "6_6") (pintype "power_in"))
    )
    (net (code "92") (name "Net-(IC4A-OUT7)") (class "Default")
      (node (ref "IC4") (pin "12") (pinfunction "OUT7_12") (pintype "open_collector"))
      (node (ref "U$4") (pin "7") (pinfunction "7_7") (pintype "power_in"))
    )
    (net (code "93") (name "Net-(IC4A-OUT8)") (class "Default")
      (node (ref "IC4") (pin "13") (pinfunction "OUT8_13") (pintype "open_collector"))
      (node (ref "U$4") (pin "8") (pinfunction "8_8") (pintype "power_in"))
    )
    (net (code "94") (name "Net-(IC4A-OUT9)") (class "Default")
      (node (ref "IC4") (pin "14") (pinfunction "OUT9_14") (pintype "open_collector"))
      (node (ref "U$4") (pin "9") (pinfunction "9_9") (pintype "power_in"))
    )
    (net (code "95") (name "Net-(IC4A-OUT10)") (class "Default")
      (node (ref "IC4") (pin "15") (pinfunction "OUT10_15") (pintype "open_collector"))
      (node (ref "U$4") (pin "10") (pinfunction "10_10") (pintype "power_in"))
    )
    (net (code "96") (name "Net-(IC4A-OUT11)") (class "Default")
      (node (ref "IC4") (pin "16") (pinfunction "OUT11_16") (pintype "open_collector"))
      (node (ref "U$4") (pin "11") (pinfunction "11_11") (pintype "power_in"))
    )
    (net (code "97") (name "Net-(IC4A-OUT12)") (class "Default")
      (node (ref "IC4") (pin "28") (pinfunction "OUT12_28") (pintype "open_collector"))
      (node (ref "U$4") (pin "23") (pinfunction "23_23") (pintype "power_in"))
    )
    (net (code "98") (name "Net-(IC4A-OUT13)") (class "Default")
      (node (ref "IC4") (pin "27") (pinfunction "OUT13_27") (pintype "open_collector"))
      (node (ref "U$4") (pin "22") (pinfunction "22_22") (pintype "power_in"))
    )
    (net (code "99") (name "Net-(IC4A-OUT14)") (class "Default")
      (node (ref "IC4") (pin "26") (pinfunction "OUT14_26") (pintype "open_collector"))
      (node (ref "U$4") (pin "21") (pinfunction "21_21") (pintype "power_in"))
    )
    (net (code "100") (name "Net-(IC4A-OUT15)") (class "Default")
      (node (ref "IC4") (pin "25") (pinfunction "OUT15_25") (pintype "open_collector"))
      (node (ref "U$4") (pin "20") (pinfunction "20_20") (pintype "power_in"))
    )
    (net (code "101") (name "Net-(IC4A-OUT16)") (class "Default")
      (node (ref "IC4") (pin "24") (pinfunction "OUT16_24") (pintype "open_collector"))
      (node (ref "U$4") (pin "19") (pinfunction "19_19") (pintype "power_in"))
    )
    (net (code "102") (name "Net-(IC4A-OUT17)") (class "Default")
      (node (ref "IC4") (pin "23") (pinfunction "OUT17_23") (pintype "open_collector"))
      (node (ref "U$4") (pin "18") (pinfunction "18_18") (pintype "power_in"))
    )
    (net (code "103") (name "Net-(IC4A-OUT18)") (class "Default")
      (node (ref "IC4") (pin "22") (pinfunction "OUT18_22") (pintype "open_collector"))
      (node (ref "U$4") (pin "17") (pinfunction "17_17") (pintype "power_in"))
    )
    (net (code "104") (name "Net-(IC4A-OUT19)") (class "Default")
      (node (ref "IC4") (pin "21") (pinfunction "OUT19_21") (pintype "open_collector"))
      (node (ref "U$4") (pin "16") (pinfunction "16_16") (pintype "power_in"))
    )
    (net (code "105") (name "Net-(IC4A-OUT20)") (class "Default")
      (node (ref "IC4") (pin "20") (pinfunction "OUT20_20") (pintype "open_collector"))
      (node (ref "U$4") (pin "15") (pinfunction "15_15") (pintype "power_in"))
    )
    (net (code "106") (name "Net-(IC4A-OUT21)") (class "Default")
      (node (ref "IC4") (pin "19") (pinfunction "OUT21_19") (pintype "open_collector"))
      (node (ref "U$4") (pin "14") (pinfunction "14_14") (pintype "power_in"))
    )
    (net (code "107") (name "Net-(IC4A-OUT22)") (class "Default")
      (node (ref "IC4") (pin "18") (pinfunction "OUT22_18") (pintype "open_collector"))
      (node (ref "U$4") (pin "13") (pinfunction "13_13") (pintype "power_in"))
    )
    (net (code "108") (name "Net-(IC4A-OUT23)") (class "Default")
      (node (ref "IC4") (pin "17") (pinfunction "OUT23_17") (pintype "open_collector"))
      (node (ref "U$4") (pin "12") (pinfunction "12_12") (pintype "power_in"))
    )
    (net (code "109") (name "unconnected-(IC4A-SOUT-Pad29)") (class "Default")
      (node (ref "IC4") (pin "29") (pinfunction "SOUT_29") (pintype "output"))
    )
    (net (code "110") (name "unconnected-(U$5-P$2-Pad2)") (class "Default")
      (node (ref "U$5") (pin "2") (pinfunction "P$2_2") (pintype "bidirectional"))
    )
  )
)
